# 3_3V_CAN_Transciever.net
KiCad netlist of a schematic drawn in Altium Designer
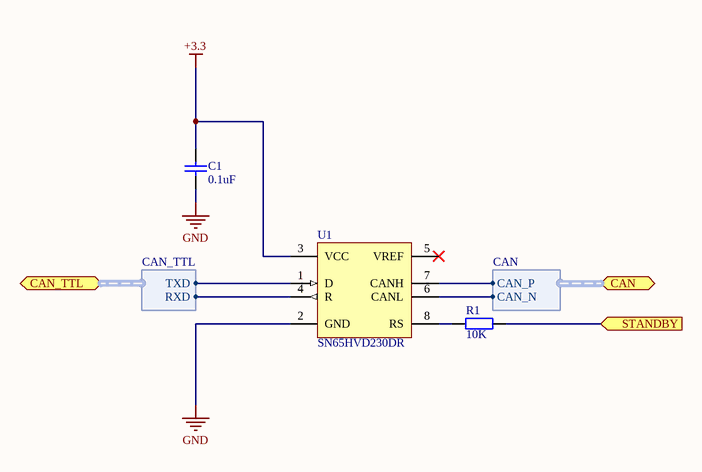
[diagram p0: 3.3V CAN Transciever.SchDoc]

(export (version "E")
  (design (tool "Eeschema 10.0.6"))
  (components
    (comp (ref "C1")
      (value "0.1uF")
      (footprint "C0603")
      (description "Capacitor")
      (fields (field (name "Comment") "Cap"))
      (libsource (lib "Miscellaneous Devices") (part "Cap"))
    )
    (comp (ref "R1")
      (value "10K")
      (footprint "R0603")
      (description "Resistor")
      (fields (field (name "Comment") "Res"))
      (libsource (lib "Miscellaneous Devices") (part "Res2"))
    )
    (comp (ref "U1")
      (value "SN65HVD230DR")
      (footprint "SN65HVD230DR")
      (description "TEXAS INSTRUMENTS - SN65HVD230DR - TRANSCEIVER CAN, 65HVD230, SOIC8")
      (libsource (lib "SN65HVD230DR") (part "SN65HVD230DR"))
    )
  )
  (nets
    (net (code "3") (name "+3.3") (class "Default")
      (node (ref "C1") (pin "1") (pinfunction "1_1") (pintype "passive"))
      (node (ref "U1") (pin "3") (pinfunction "VCC_3") (pintype "power_in"))
    )
    (net (code "4") (name "/CAN_N") (class "Default")
      (node (ref "U1") (pin "6") (pinfunction "CANL_6") (pintype "passive"))
    )
    (net (code "5") (name "/CAN_P") (class "Default")
      (node (ref "U1") (pin "7") (pinfunction "CANH_7") (pintype "passive"))
    )
    (net (code "6") (name "/RXD") (class "Default")
      (node (ref "U1") (pin "4") (pinfunction "R_4") (pintype "output"))
    )
    (net (code "7") (name "/STANDBY") (class "Default")
      (node (ref "R1") (pin "1") (pinfunction "1_1") (pintype "passive"))
    )
    (net (code "8") (name "/TXD") (class "Default")
      (node (ref "U1") (pin "1") (pinfunction "D_1") (pintype "input"))
    )
    (net (code "11") (name "GND") (class "Default")
      (node (ref "C1") (pin "2") (pinfunction "2_2") (pintype "passive"))
      (node (ref "U1") (pin "2") (pinfunction "GND_2") (pintype "power_in"))
    )
    (net (code "12") (name "Net-(U1-RS)") (class "Default")
      (node (ref "R1") (pin "2") (pinfunction "2_2") (pintype "passive"))
      (node (ref "U1") (pin "8") (pinfunction "RS_8") (pintype "passive"))
    )
    (net (code "13") (name "unconnected-(U1-VREF-Pad5)") (class "Default")
      (node (ref "U1") (pin "5") (pinfunction "VREF_5") (pintype "passive+no_connect"))
    )
  )
)
